# jetson-nano.net
KiCad netlist of a schematic drawn in Altium Designer
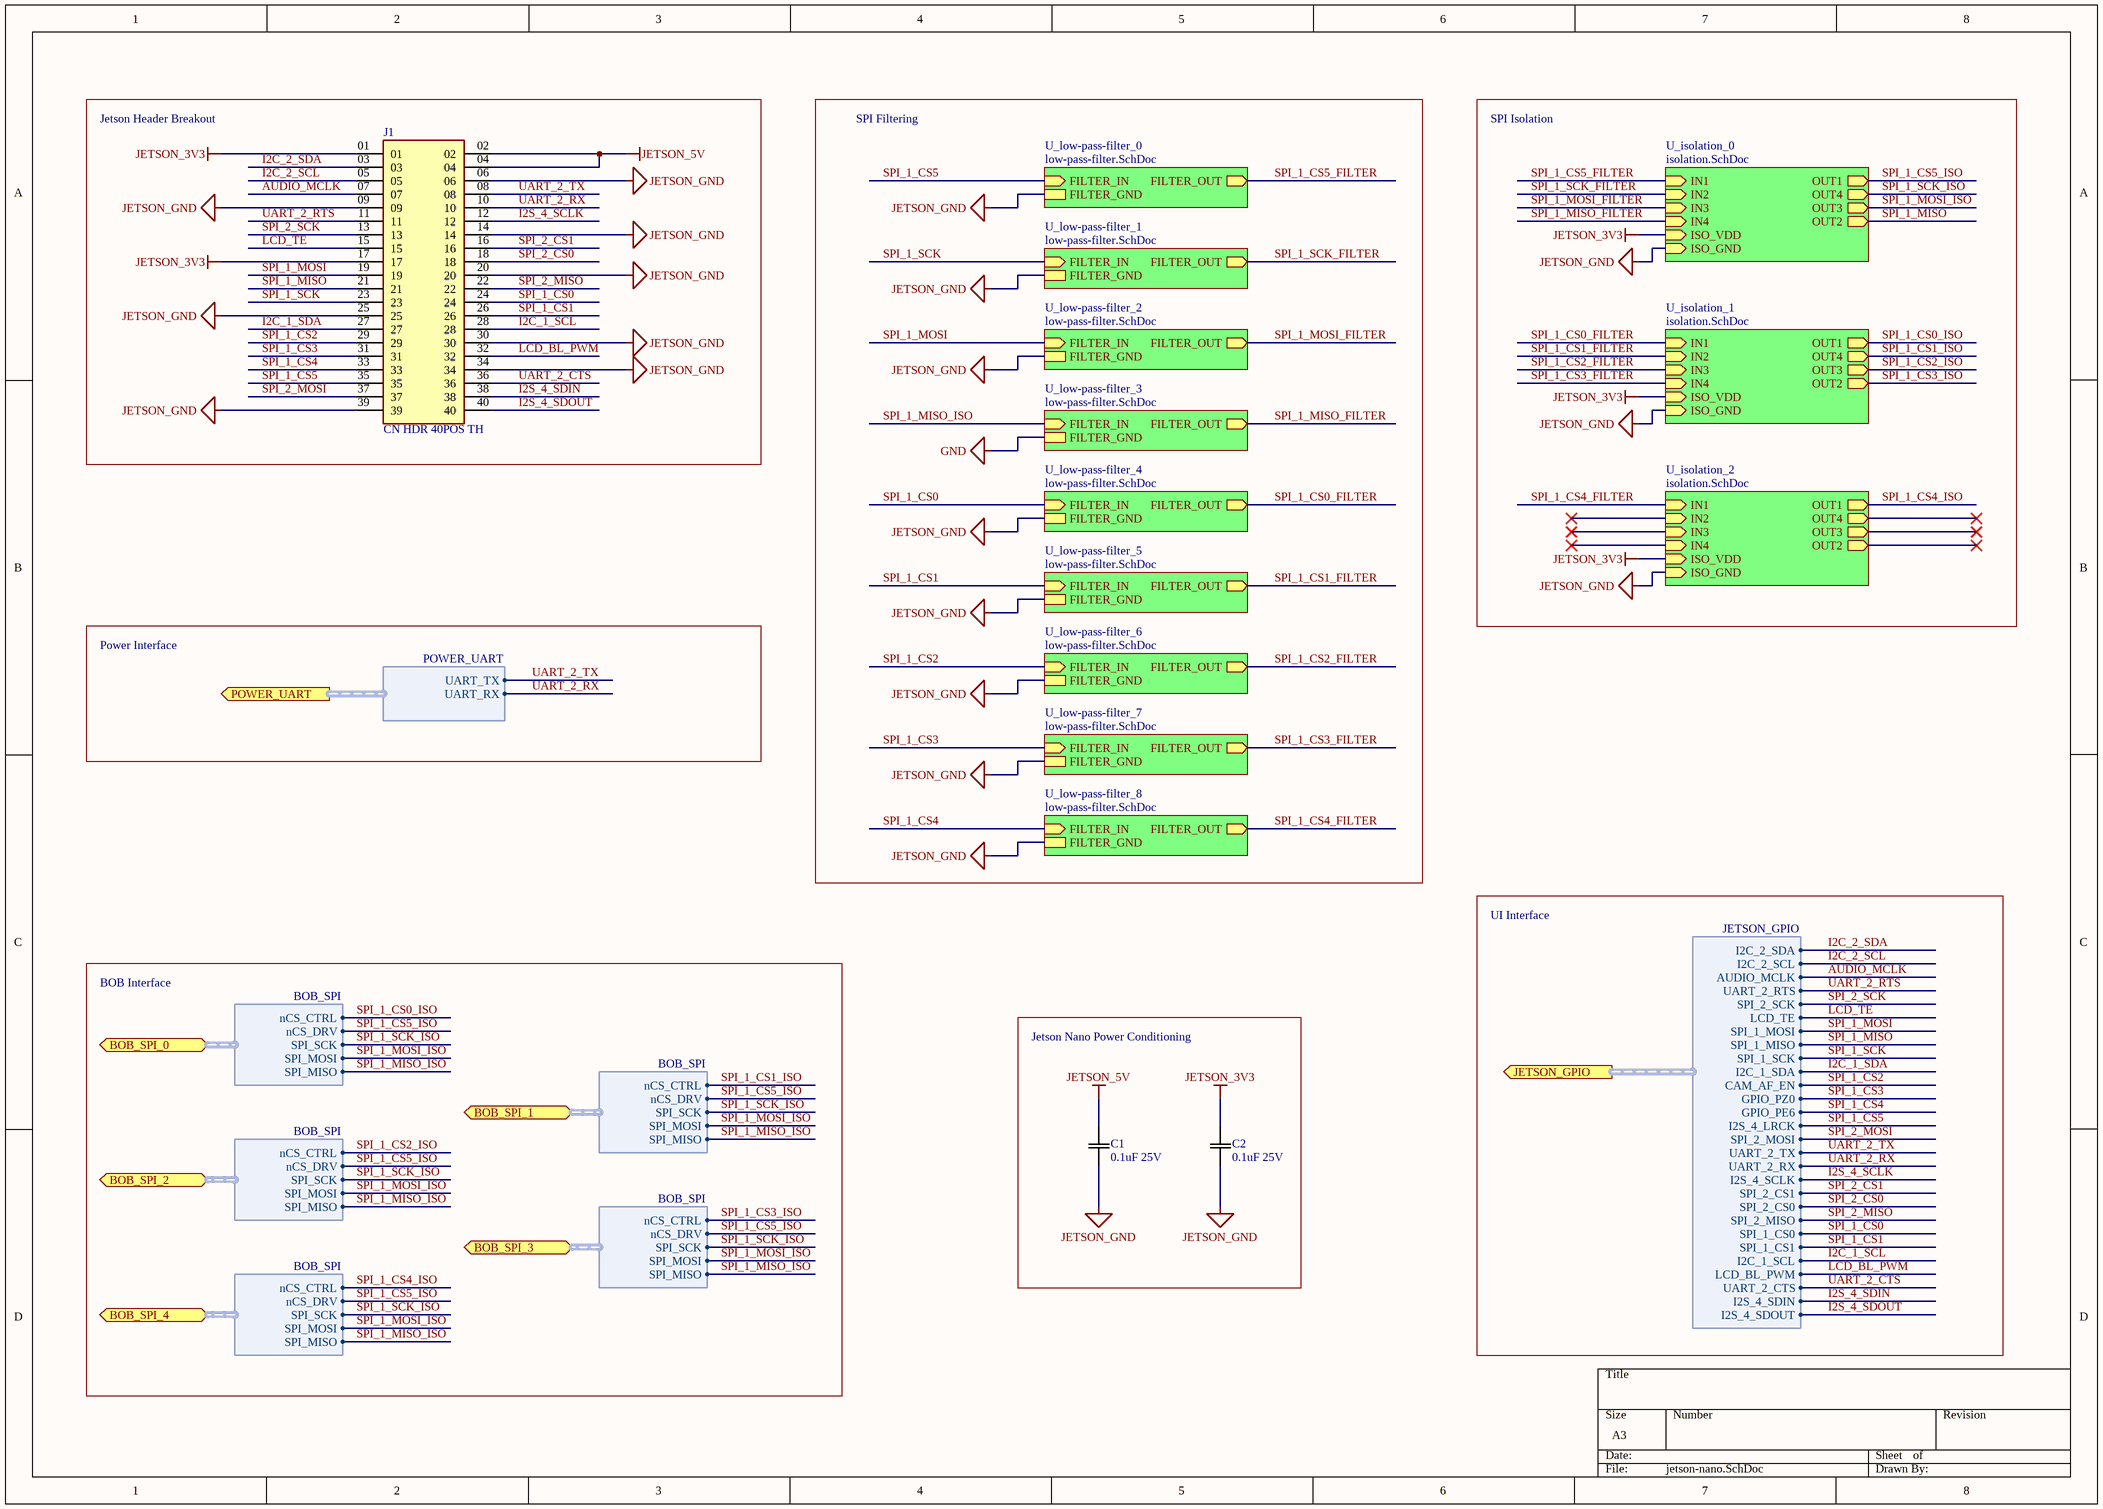
[diagram p0: jetson-nano.SchDoc]

(export (version "E")
  (design (tool "Eeschema 10.0.6"))
  (components
    (comp (ref "C1")
      (value "0.1uF 25V")
      (footprint "0805")
      (description "CAP CER 0.1UF 25V X7R 0805/0603")
      (fields (field (name "TOLERANCE") "10%"))
      (libsource (lib "AltiumLibraries") (part "CAP 0.1uF 25V"))
    )
    (comp (ref "C2")
      (value "0.1uF 25V")
      (footprint "0805")
      (description "CAP CER 0.1UF 25V X7R 0805/0603")
      (fields (field (name "TOLERANCE") "10%"))
      (libsource (lib "AltiumLibraries") (part "CAP 0.1uF 25V"))
    )
    (comp (ref "J1")
      (value "CN HDR 40POS TH")
      (footprint "SAMTEC_SSQ-120-22-G-D")
      (description "SSQ - Samtec 2.54mm Square Tail Dual Row Socket Strip 8.5mm Profile")
      (fields (field (name "MF") "Samtec") (field (name "MP") "SSQ-120-22-G-D"))
      (libsource (lib "AltiumLibraries") (part "CN HDR 40POS TH"))
    )
  )
  (nets
    (net (code "4") (name "/AUDIO_MCLK") (class "Default")
      (node (ref "J1") (pin "07") (pinfunction "07_07") (pintype "passive"))
    )
    (net (code "5") (name "/I2C_1_SCL") (class "Default")
      (node (ref "J1") (pin "28") (pinfunction "28_28") (pintype "passive"))
    )
    (net (code "6") (name "/I2C_1_SDA") (class "Default")
      (node (ref "J1") (pin "27") (pinfunction "27_27") (pintype "passive"))
    )
    (net (code "7") (name "/I2C_2_SCL") (class "Default")
      (node (ref "J1") (pin "05") (pinfunction "05_05") (pintype "passive"))
    )
    (net (code "8") (name "/I2C_2_SDA") (class "Default")
      (node (ref "J1") (pin "03") (pinfunction "03_03") (pintype "passive"))
    )
    (net (code "9") (name "/I2S_4_SCLK") (class "Default")
      (node (ref "J1") (pin "12") (pinfunction "12_12") (pintype "passive"))
    )
    (net (code "10") (name "/I2S_4_SDIN") (class "Default")
      (node (ref "J1") (pin "38") (pinfunction "38_38") (pintype "passive"))
    )
    (net (code "11") (name "/I2S_4_SDOUT") (class "Default")
      (node (ref "J1") (pin "40") (pinfunction "40_40") (pintype "passive"))
    )
    (net (code "15") (name "/LCD_BL_PWM") (class "Default")
      (node (ref "J1") (pin "32") (pinfunction "32_32") (pintype "passive"))
    )
    (net (code "16") (name "/LCD_TE") (class "Default")
      (node (ref "J1") (pin "15") (pinfunction "15_15") (pintype "passive"))
    )
    (net (code "20") (name "/SPI_1_CS0") (class "Default")
      (node (ref "J1") (pin "24") (pinfunction "24_24") (pintype "passive"))
    )
    (net (code "23") (name "/SPI_1_CS1") (class "Default")
      (node (ref "J1") (pin "26") (pinfunction "26_26") (pintype "passive"))
    )
    (net (code "26") (name "/SPI_1_CS2") (class "Default")
      (node (ref "J1") (pin "29") (pinfunction "29_29") (pintype "passive"))
    )
    (net (code "29") (name "/SPI_1_CS3") (class "Default")
      (node (ref "J1") (pin "31") (pinfunction "31_31") (pintype "passive"))
    )
    (net (code "32") (name "/SPI_1_CS4") (class "Default")
      (node (ref "J1") (pin "33") (pinfunction "33_33") (pintype "passive"))
    )
    (net (code "35") (name "/SPI_1_CS5") (class "Default")
      (node (ref "J1") (pin "35") (pinfunction "35_35") (pintype "passive"))
    )
    (net (code "38") (name "/SPI_1_MISO") (class "Default")
      (node (ref "J1") (pin "21") (pinfunction "21_21") (pintype "passive"))
    )
    (net (code "41") (name "/SPI_1_MOSI") (class "Default")
      (node (ref "J1") (pin "19") (pinfunction "19_19") (pintype "passive"))
    )
    (net (code "44") (name "/SPI_1_SCK") (class "Default")
      (node (ref "J1") (pin "23") (pinfunction "23_23") (pintype "passive"))
    )
    (net (code "47") (name "/SPI_2_CS0") (class "Default")
      (node (ref "J1") (pin "18") (pinfunction "18_18") (pintype "passive"))
    )
    (net (code "48") (name "/SPI_2_CS1") (class "Default")
      (node (ref "J1") (pin "16") (pinfunction "16_16") (pintype "passive"))
    )
    (net (code "49") (name "/SPI_2_MISO") (class "Default")
      (node (ref "J1") (pin "22") (pinfunction "22_22") (pintype "passive"))
    )
    (net (code "50") (name "/SPI_2_MOSI") (class "Default")
      (node (ref "J1") (pin "37") (pinfunction "37_37") (pintype "passive"))
    )
    (net (code "51") (name "/SPI_2_SCK") (class "Default")
      (node (ref "J1") (pin "13") (pinfunction "13_13") (pintype "passive"))
    )
    (net (code "52") (name "/UART_2_CTS") (class "Default")
      (node (ref "J1") (pin "36") (pinfunction "36_36") (pintype "passive"))
    )
    (net (code "53") (name "/UART_2_RTS") (class "Default")
      (node (ref "J1") (pin "11") (pinfunction "11_11") (pintype "passive"))
    )
    (net (code "54") (name "/UART_2_RX") (class "Default")
      (node (ref "J1") (pin "10") (pinfunction "10_10") (pintype "passive"))
    )
    (net (code "55") (name "/UART_2_TX") (class "Default")
      (node (ref "J1") (pin "08") (pinfunction "08_08") (pintype "passive"))
    )
    (net (code "60") (name "JETSON_3V3") (class "Default")
      (node (ref "C2") (pin "1") (pinfunction "C1_1") (pintype "passive"))
      (node (ref "J1") (pin "01") (pinfunction "01_01") (pintype "passive"))
      (node (ref "J1") (pin "17") (pinfunction "17_17") (pintype "passive"))
    )
    (net (code "61") (name "JETSON_5V") (class "Default")
      (node (ref "C1") (pin "1") (pinfunction "C1_1") (pintype "passive"))
      (node (ref "J1") (pin "02") (pinfunction "02_02") (pintype "passive"))
      (node (ref "J1") (pin "04") (pinfunction "04_04") (pintype "passive"))
    )
    (net (code "62") (name "JETSON_GND") (class "Default")
      (node (ref "C1") (pin "2") (pinfunction "C2_2") (pintype "passive"))
      (node (ref "C2") (pin "2") (pinfunction "C2_2") (pintype "passive"))
      (node (ref "J1") (pin "06") (pinfunction "06_06") (pintype "passive"))
      (node (ref "J1") (pin "09") (pinfunction "09_09") (pintype "passive"))
      (node (ref "J1") (pin "14") (pinfunction "14_14") (pintype "passive"))
      (node (ref "J1") (pin "20") (pinfunction "20_20") (pintype "passive"))
      (node (ref "J1") (pin "25") (pinfunction "25_25") (pintype "passive"))
      (node (ref "J1") (pin "30") (pinfunction "30_30") (pintype "passive"))
      (node (ref "J1") (pin "34") (pinfunction "34_34") (pintype "passive"))
      (node (ref "J1") (pin "39") (pinfunction "39_39") (pintype "passive"))
    )
  )
)
